# IPM_24V_24V.net
KiCad netlist of a schematic drawn in EasyEDA Pro
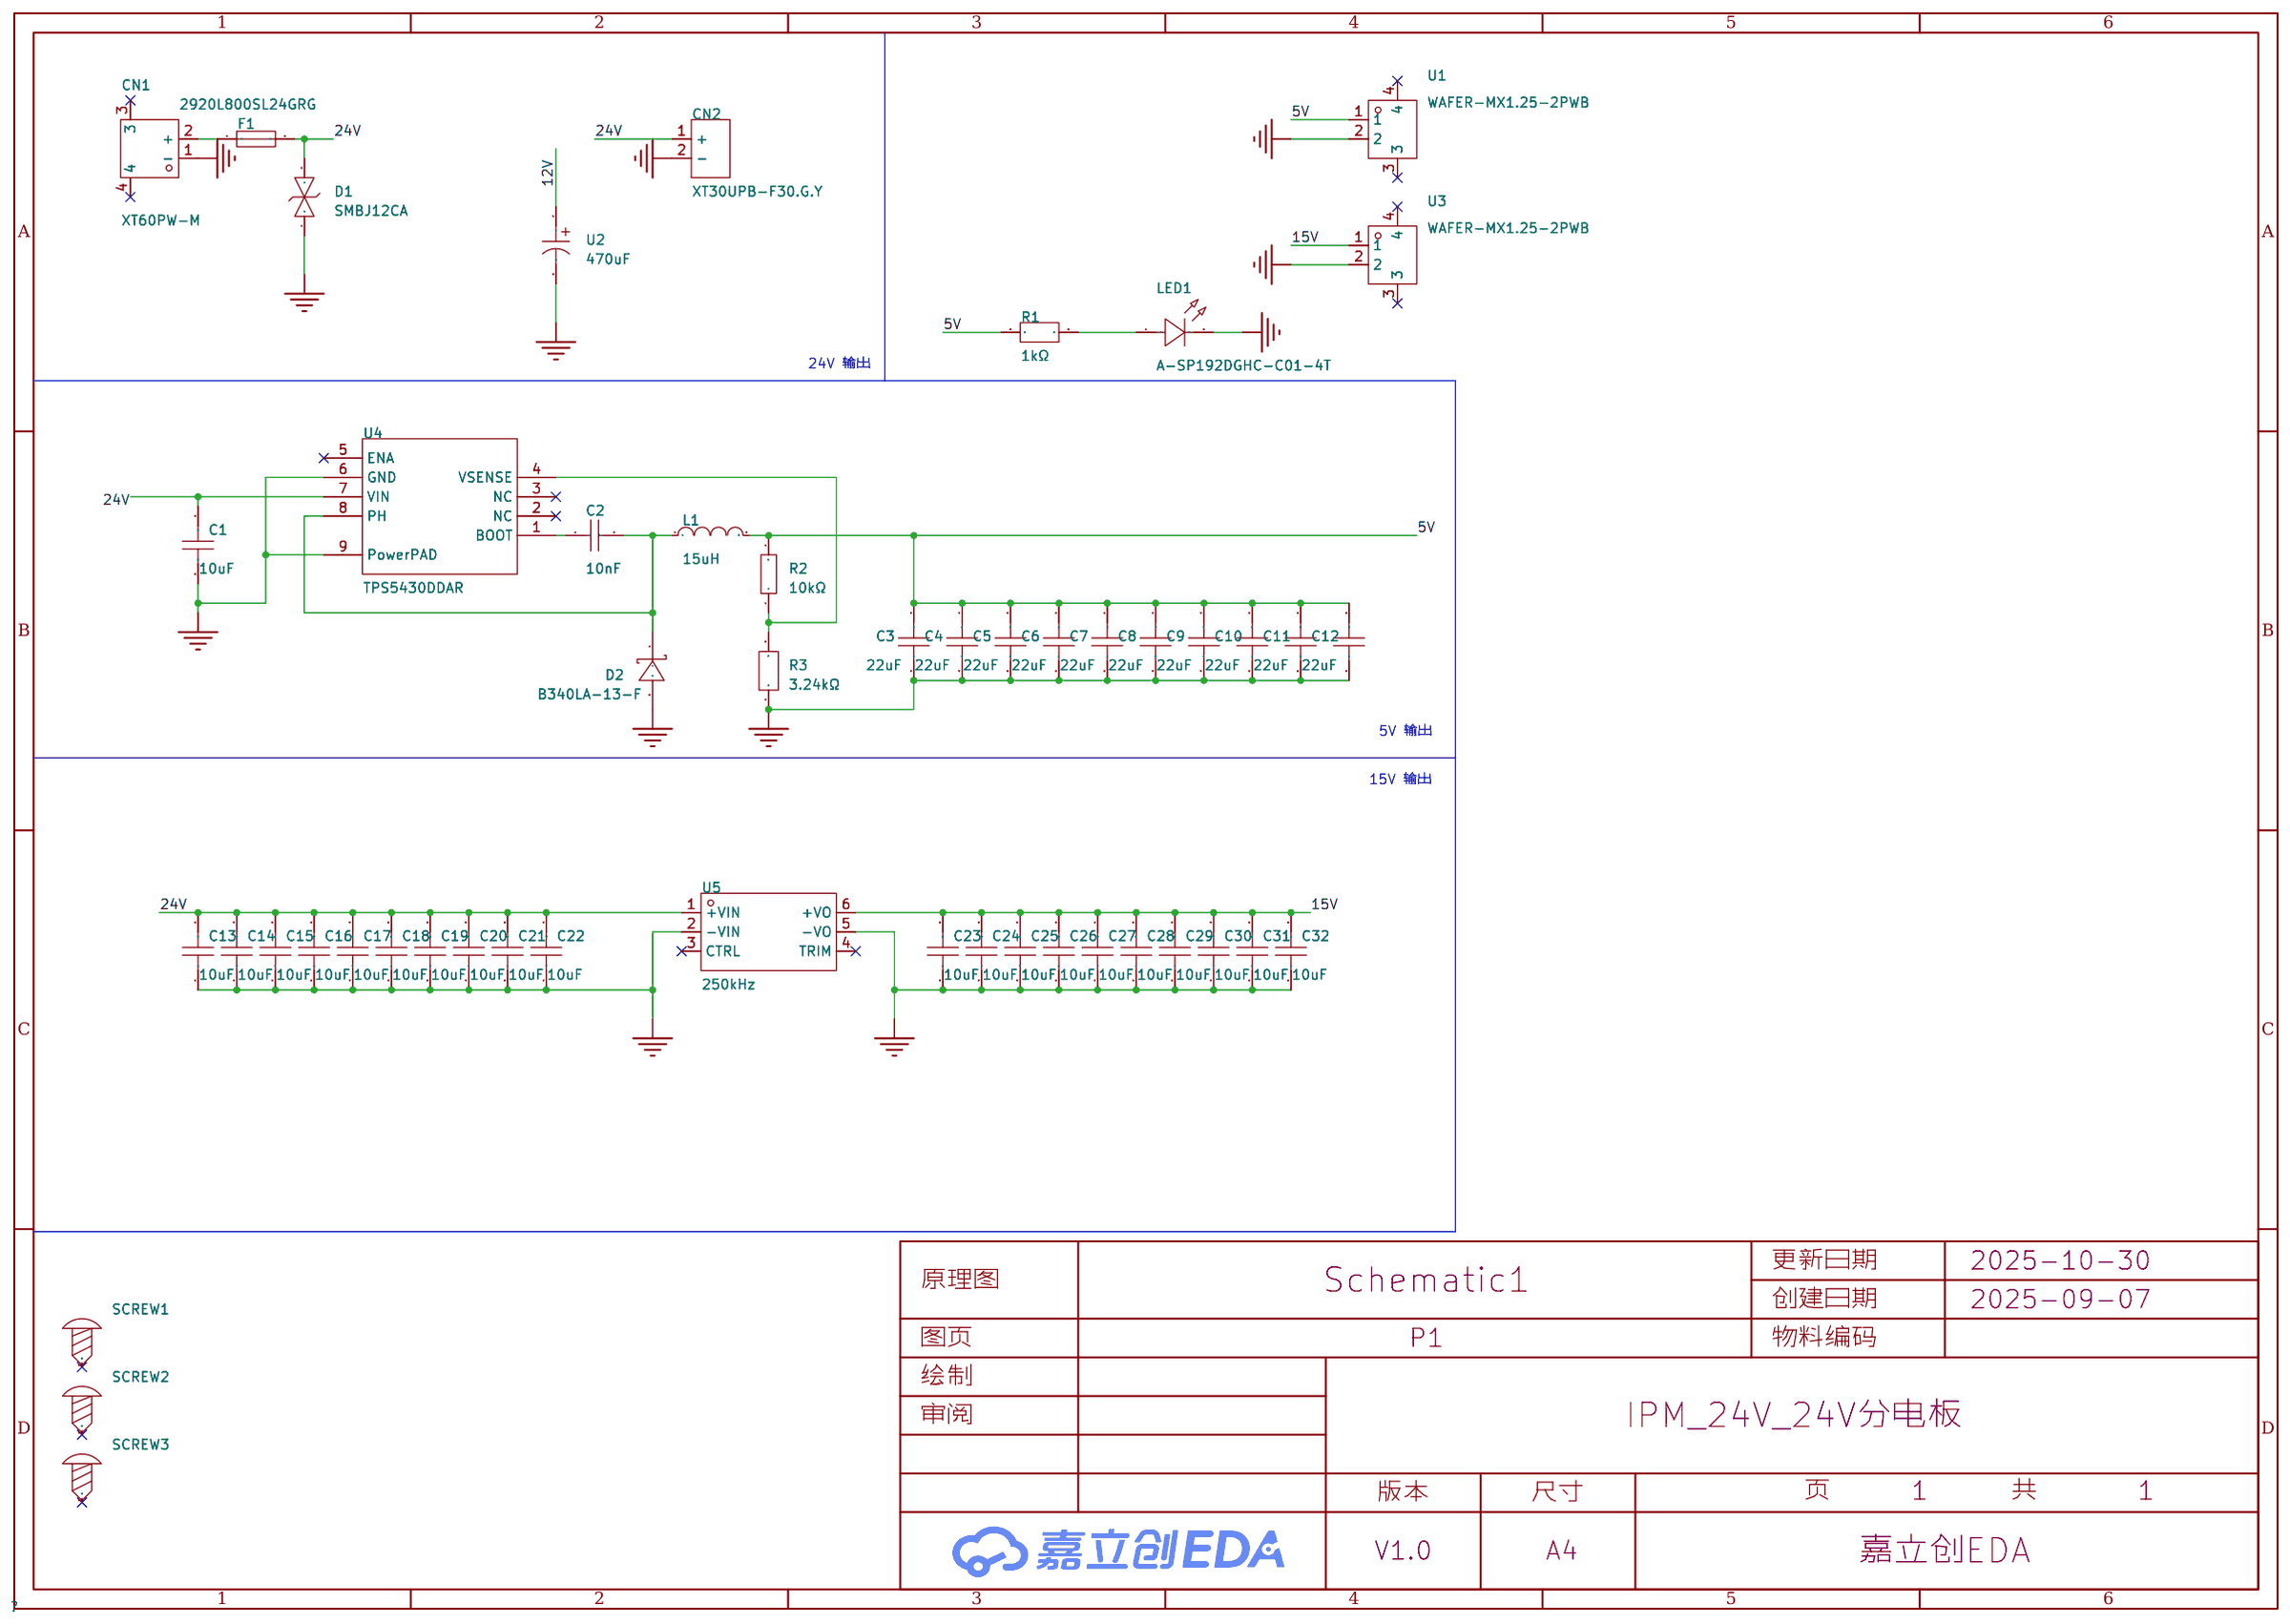
[diagram p0: schematic sheet]

(export (version "E")
  (design (tool "Eeschema 10.0.6"))
  (components
    (comp (ref "C1")
      (value "10uF")
      (footprint "easyedapro:C1206")
      (description "容值:10uF;精度:±10%;额定电压:50V;温度系数:X7R;")
      (fields
        (field (name "Manufacturer Part") "CL31B106KBHNNNE")
        (field (name "Manufacturer") "SAMSUNG(三星)")
      )
      (libsource (lib "easyedapro") (part "CL31B106KBHNNNE"))
    )
    (comp (ref "C2")
      (value "10nF")
      (footprint "easyedapro:C0603")
      (description "容值:10nF;精度:±10%;额定电压:50V;温度系数:X7R;")
      (fields
        (field (name "Manufacturer Part") "CL10B103KB8NNNC")
        (field (name "Manufacturer") "SAMSUNG(三星)")
      )
      (libsource (lib "easyedapro") (part "CL10B103KB8NNNC"))
    )
    (comp (ref "C3")
      (value "22uF")
      (footprint "easyedapro:C0603")
      (description "容值:22uF;精度:±20%;额定电压:16V;温度系数:X5R;")
      (fields
        (field (name "Manufacturer Part") "CL10A226MO7JZNC")
        (field (name "Manufacturer") "SAMSUNG(三星)")
      )
      (libsource (lib "easyedapro") (part "CL10A226MO7JZNC"))
    )
    (comp (ref "C4")
      (value "22uF")
      (footprint "easyedapro:C0603")
      (description "容值:22uF;精度:±20%;额定电压:16V;温度系数:X5R;")
      (fields
        (field (name "Manufacturer Part") "CL10A226MO7JZNC")
        (field (name "Manufacturer") "SAMSUNG(三星)")
      )
      (libsource (lib "easyedapro") (part "CL10A226MO7JZNC"))
    )
    (comp (ref "C5")
      (value "22uF")
      (footprint "easyedapro:C0603")
      (description "容值:22uF;精度:±20%;额定电压:16V;温度系数:X5R;")
      (fields
        (field (name "Manufacturer Part") "CL10A226MO7JZNC")
        (field (name "Manufacturer") "SAMSUNG(三星)")
      )
      (libsource (lib "easyedapro") (part "CL10A226MO7JZNC"))
    )
    (comp (ref "C6")
      (value "22uF")
      (footprint "easyedapro:C0603")
      (description "容值:22uF;精度:±20%;额定电压:16V;温度系数:X5R;")
      (fields
        (field (name "Manufacturer Part") "CL10A226MO7JZNC")
        (field (name "Manufacturer") "SAMSUNG(三星)")
      )
      (libsource (lib "easyedapro") (part "CL10A226MO7JZNC"))
    )
    (comp (ref "C7")
      (value "22uF")
      (footprint "easyedapro:C0603")
      (description "容值:22uF;精度:±20%;额定电压:16V;温度系数:X5R;")
      (fields
        (field (name "Manufacturer Part") "CL10A226MO7JZNC")
        (field (name "Manufacturer") "SAMSUNG(三星)")
      )
      (libsource (lib "easyedapro") (part "CL10A226MO7JZNC"))
    )
    (comp (ref "C8")
      (value "22uF")
      (footprint "easyedapro:C0603")
      (description "容值:22uF;精度:±20%;额定电压:16V;温度系数:X5R;")
      (fields
        (field (name "Manufacturer Part") "CL10A226MO7JZNC")
        (field (name "Manufacturer") "SAMSUNG(三星)")
      )
      (libsource (lib "easyedapro") (part "CL10A226MO7JZNC"))
    )
    (comp (ref "C9")
      (value "22uF")
      (footprint "easyedapro:C0603")
      (description "容值:22uF;精度:±20%;额定电压:16V;温度系数:X5R;")
      (fields
        (field (name "Manufacturer Part") "CL10A226MO7JZNC")
        (field (name "Manufacturer") "SAMSUNG(三星)")
      )
      (libsource (lib "easyedapro") (part "CL10A226MO7JZNC"))
    )
    (comp (ref "C10")
      (value "22uF")
      (footprint "easyedapro:C0603")
      (description "容值:22uF;精度:±20%;额定电压:16V;温度系数:X5R;")
      (fields
        (field (name "Manufacturer Part") "CL10A226MO7JZNC")
        (field (name "Manufacturer") "SAMSUNG(三星)")
      )
      (libsource (lib "easyedapro") (part "CL10A226MO7JZNC"))
    )
    (comp (ref "C11")
      (value "22uF")
      (footprint "easyedapro:C0603")
      (description "容值:22uF;精度:±20%;额定电压:16V;温度系数:X5R;")
      (fields
        (field (name "Manufacturer Part") "CL10A226MO7JZNC")
        (field (name "Manufacturer") "SAMSUNG(三星)")
      )
      (libsource (lib "easyedapro") (part "CL10A226MO7JZNC"))
    )
    (comp (ref "C12")
      (value "22uF")
      (footprint "easyedapro:C0603")
      (description "容值:22uF;精度:±20%;额定电压:16V;温度系数:X5R;")
      (fields
        (field (name "Manufacturer Part") "CL10A226MO7JZNC")
        (field (name "Manufacturer") "SAMSUNG(三星)")
      )
      (libsource (lib "easyedapro") (part "CL10A226MO7JZNC"))
    )
    (comp (ref "C13")
      (value "10uF")
      (footprint "easyedapro:C1206")
      (description "容值:10uF;精度:±10%;额定电压:50V;温度系数:X7R;")
      (fields
        (field (name "Manufacturer Part") "CL31B106KBHNNNE")
        (field (name "Manufacturer") "SAMSUNG(三星)")
      )
      (libsource (lib "easyedapro") (part "CL31B106KBHNNNE"))
    )
    (comp (ref "C14")
      (value "10uF")
      (footprint "easyedapro:C1206")
      (description "容值:10uF;精度:±10%;额定电压:50V;温度系数:X7R;")
      (fields
        (field (name "Manufacturer Part") "CL31B106KBHNNNE")
        (field (name "Manufacturer") "SAMSUNG(三星)")
      )
      (libsource (lib "easyedapro") (part "CL31B106KBHNNNE"))
    )
    (comp (ref "C15")
      (value "10uF")
      (footprint "easyedapro:C1206")
      (description "容值:10uF;精度:±10%;额定电压:50V;温度系数:X7R;")
      (fields
        (field (name "Manufacturer Part") "CL31B106KBHNNNE")
        (field (name "Manufacturer") "SAMSUNG(三星)")
      )
      (libsource (lib "easyedapro") (part "CL31B106KBHNNNE"))
    )
    (comp (ref "C16")
      (value "10uF")
      (footprint "easyedapro:C1206")
      (description "容值:10uF;精度:±10%;额定电压:50V;温度系数:X7R;")
      (fields
        (field (name "Manufacturer Part") "CL31B106KBHNNNE")
        (field (name "Manufacturer") "SAMSUNG(三星)")
      )
      (libsource (lib "easyedapro") (part "CL31B106KBHNNNE"))
    )
    (comp (ref "C17")
      (value "10uF")
      (footprint "easyedapro:C1206")
      (description "容值:10uF;精度:±10%;额定电压:50V;温度系数:X7R;")
      (fields
        (field (name "Manufacturer Part") "CL31B106KBHNNNE")
        (field (name "Manufacturer") "SAMSUNG(三星)")
      )
      (libsource (lib "easyedapro") (part "CL31B106KBHNNNE"))
    )
    (comp (ref "C18")
      (value "10uF")
      (footprint "easyedapro:C1206")
      (description "容值:10uF;精度:±10%;额定电压:50V;温度系数:X7R;")
      (fields
        (field (name "Manufacturer Part") "CL31B106KBHNNNE")
        (field (name "Manufacturer") "SAMSUNG(三星)")
      )
      (libsource (lib "easyedapro") (part "CL31B106KBHNNNE"))
    )
    (comp (ref "C19")
      (value "10uF")
      (footprint "easyedapro:C1206")
      (description "容值:10uF;精度:±10%;额定电压:50V;温度系数:X7R;")
      (fields
        (field (name "Manufacturer Part") "CL31B106KBHNNNE")
        (field (name "Manufacturer") "SAMSUNG(三星)")
      )
      (libsource (lib "easyedapro") (part "CL31B106KBHNNNE"))
    )
    (comp (ref "C20")
      (value "10uF")
      (footprint "easyedapro:C1206")
      (description "容值:10uF;精度:±10%;额定电压:50V;温度系数:X7R;")
      (fields
        (field (name "Manufacturer Part") "CL31B106KBHNNNE")
        (field (name "Manufacturer") "SAMSUNG(三星)")
      )
      (libsource (lib "easyedapro") (part "CL31B106KBHNNNE"))
    )
    (comp (ref "C21")
      (value "10uF")
      (footprint "easyedapro:C1206")
      (description "容值:10uF;精度:±10%;额定电压:50V;温度系数:X7R;")
      (fields
        (field (name "Manufacturer Part") "CL31B106KBHNNNE")
        (field (name "Manufacturer") "SAMSUNG(三星)")
      )
      (libsource (lib "easyedapro") (part "CL31B106KBHNNNE"))
    )
    (comp (ref "C22")
      (value "10uF")
      (footprint "easyedapro:C1206")
      (description "容值:10uF;精度:±10%;额定电压:50V;温度系数:X7R;")
      (fields
        (field (name "Manufacturer Part") "CL31B106KBHNNNE")
        (field (name "Manufacturer") "SAMSUNG(三星)")
      )
      (libsource (lib "easyedapro") (part "CL31B106KBHNNNE"))
    )
    (comp (ref "C23")
      (value "10uF")
      (footprint "easyedapro:C1206")
      (description "容值:10uF;精度:±10%;额定电压:50V;温度系数:X7R;")
      (fields
        (field (name "Manufacturer Part") "CL31B106KBHNNNE")
        (field (name "Manufacturer") "SAMSUNG(三星)")
      )
      (libsource (lib "easyedapro") (part "CL31B106KBHNNNE"))
    )
    (comp (ref "C24")
      (value "10uF")
      (footprint "easyedapro:C1206")
      (description "容值:10uF;精度:±10%;额定电压:50V;温度系数:X7R;")
      (fields
        (field (name "Manufacturer Part") "CL31B106KBHNNNE")
        (field (name "Manufacturer") "SAMSUNG(三星)")
      )
      (libsource (lib "easyedapro") (part "CL31B106KBHNNNE"))
    )
    (comp (ref "C25")
      (value "10uF")
      (footprint "easyedapro:C1206")
      (description "容值:10uF;精度:±10%;额定电压:50V;温度系数:X7R;")
      (fields
        (field (name "Manufacturer Part") "CL31B106KBHNNNE")
        (field (name "Manufacturer") "SAMSUNG(三星)")
      )
      (libsource (lib "easyedapro") (part "CL31B106KBHNNNE"))
    )
    (comp (ref "C26")
      (value "10uF")
      (footprint "easyedapro:C1206")
      (description "容值:10uF;精度:±10%;额定电压:50V;温度系数:X7R;")
      (fields
        (field (name "Manufacturer Part") "CL31B106KBHNNNE")
        (field (name "Manufacturer") "SAMSUNG(三星)")
      )
      (libsource (lib "easyedapro") (part "CL31B106KBHNNNE"))
    )
    (comp (ref "C27")
      (value "10uF")
      (footprint "easyedapro:C1206")
      (description "容值:10uF;精度:±10%;额定电压:50V;温度系数:X7R;")
      (fields
        (field (name "Manufacturer Part") "CL31B106KBHNNNE")
        (field (name "Manufacturer") "SAMSUNG(三星)")
      )
      (libsource (lib "easyedapro") (part "CL31B106KBHNNNE"))
    )
    (comp (ref "C28")
      (value "10uF")
      (footprint "easyedapro:C1206")
      (description "容值:10uF;精度:±10%;额定电压:50V;温度系数:X7R;")
      (fields
        (field (name "Manufacturer Part") "CL31B106KBHNNNE")
        (field (name "Manufacturer") "SAMSUNG(三星)")
      )
      (libsource (lib "easyedapro") (part "CL31B106KBHNNNE"))
    )
    (comp (ref "C29")
      (value "10uF")
      (footprint "easyedapro:C1206")
      (description "容值:10uF;精度:±10%;额定电压:50V;温度系数:X7R;")
      (fields
        (field (name "Manufacturer Part") "CL31B106KBHNNNE")
        (field (name "Manufacturer") "SAMSUNG(三星)")
      )
      (libsource (lib "easyedapro") (part "CL31B106KBHNNNE"))
    )
    (comp (ref "C30")
      (value "10uF")
      (footprint "easyedapro:C1206")
      (description "容值:10uF;精度:±10%;额定电压:50V;温度系数:X7R;")
      (fields
        (field (name "Manufacturer Part") "CL31B106KBHNNNE")
        (field (name "Manufacturer") "SAMSUNG(三星)")
      )
      (libsource (lib "easyedapro") (part "CL31B106KBHNNNE"))
    )
    (comp (ref "C31")
      (value "10uF")
      (footprint "easyedapro:C1206")
      (description "容值:10uF;精度:±10%;额定电压:50V;温度系数:X7R;")
      (fields
        (field (name "Manufacturer Part") "CL31B106KBHNNNE")
        (field (name "Manufacturer") "SAMSUNG(三星)")
      )
      (libsource (lib "easyedapro") (part "CL31B106KBHNNNE"))
    )
    (comp (ref "C32")
      (value "10uF")
      (footprint "easyedapro:C1206")
      (description "容值:10uF;精度:±10%;额定电压:50V;温度系数:X7R;")
      (fields
        (field (name "Manufacturer Part") "CL31B106KBHNNNE")
        (field (name "Manufacturer") "SAMSUNG(三星)")
      )
      (libsource (lib "easyedapro") (part "CL31B106KBHNNNE"))
    )
    (comp (ref "CN1")
      (value "XT60PW-M")
      (footprint "easyedapro:CONN-TH_XT60PW-M")
      (description "类别:-;类型1:-;")
      (fields (field (name "Manufacturer") "AMASS(艾迈斯)"))
      (libsource (lib "easyedapro") (part "XT60PW-M"))
    )
    (comp (ref "CN2")
      (value "XT30UPB-F30.G.Y")
      (footprint "easyedapro:CONN-TH_XT30UPB-F")
      (description "类别:-;类型1:-;")
      (fields (field (name "Manufacturer") "AMASS(艾迈斯)"))
      (libsource (lib "easyedapro") (part "XT30UPB-F"))
    )
    (comp (ref "D1")
      (value "SMBJ12CA")
      (footprint "easyedapro:SMB_L4.6-W3.6-LS5.4-BI")
      (fields (field (name "Manufacturer") "R+O(宏嘉诚)"))
      (libsource (lib "easyedapro") (part "SMBJ12CA_C19077566"))
    )
    (comp (ref "D2")
      (value "B340LA-13-F")
      (footprint "easyedapro:SMA_L4.3-W2.6-LS5.2-RD")
      (description "正向压降(Vf):450mV@3A;直流反向耐压(Vr):40V;平均整流电流(Io):3A;")
      (fields (field (name "Manufacturer") "DIODES(美台)"))
      (libsource (lib "easyedapro") (part "B340LA-13-F"))
    )
    (comp (ref "F1")
      (value "2920L800SL24GRG")
      (footprint "easyedapro:F2920")
      (description "耐压(Vmax):24V;最大电流(Imax):50A;保持电流(Ihold):8A;跳闸电流(Itrip):16A;")
      (fields (field (name "Manufacturer") "LUTE(陆特)"))
      (libsource (lib "easyedapro") (part "2920L800SL24GRG"))
    )
    (comp (ref "L1")
      (value "15uH")
      (footprint "easyedapro:IND-SMD_L7.0-W6.6_FXL0630")
      (description "电感值:15uH;精度:±20%;额定电流:3A;饱和电流(Isat):4A;类型:一体成型电感;")
      (fields (field (name "Manufacturer Part") "FXL0630-150-M") (field (name "Manufacturer") "cjiang(长江微电)"))
      (libsource (lib "easyedapro") (part "FXL0630-150-M"))
    )
    (comp (ref "LED1")
      (value "A-SP192DGHC-C01-4T")
      (footprint "easyedapro:LED0603-FD")
      (fields (field (name "Manufacturer") "Amicc(欧密格光电)"))
      (libsource (lib "easyedapro") (part "A-SP192DGHC-C01-4T"))
    )
    (comp (ref "R1")
      (value "1kΩ")
      (footprint "easyedapro:R0603")
      (description "电阻类型:厚膜电阻;阻值:1kΩ;精度:±1%;功率:100mW;工作电压:75V;温度系数:±100ppm/°C;")
      (fields (field (name "Manufacturer Part") "FRC0603F1001TS") (field (name "Manufacturer") "FOJAN(富捷)"))
      (libsource (lib "easyedapro") (part "FRC0603F1001TS"))
    )
    (comp (ref "R2")
      (value "10kΩ")
      (footprint "easyedapro:R0603")
      (description "电阻类型:厚膜电阻;阻值:10kΩ;精度:±1%;功率:100mW;工作电压:75V;温度系数:±100ppm/°C;")
      (fields
        (field (name "Manufacturer Part") "0603WAF1002T5E")
        (field (name "Manufacturer") "UNI-ROYAL(厚声)")
      )
      (libsource (lib "easyedapro") (part "0603WAF1002T5E"))
    )
    (comp (ref "R3")
      (value "3.24kΩ")
      (footprint "easyedapro:R0603")
      (description "电阻类型:厚膜电阻;阻值:3.24kΩ;精度:±1%;功率:100mW;工作电压:75V;温度系数:±100ppm/°C;")
      (fields (field (name "Manufacturer Part") "FRC0603F3241TS") (field (name "Manufacturer") "FOJAN(富捷)"))
      (libsource (lib "easyedapro") (part "FRC0603F3241TS"))
    )
    (comp (ref "SCREW1")
      (value "~")
      (footprint "easyedapro:M2螺丝")
      (libsource (lib "easyedapro") (part "螺丝孔"))
    )
    (comp (ref "SCREW2")
      (value "~")
      (footprint "easyedapro:M2螺丝")
      (libsource (lib "easyedapro") (part "螺丝孔"))
    )
    (comp (ref "SCREW3")
      (value "~")
      (footprint "easyedapro:M2螺丝")
      (libsource (lib "easyedapro") (part "螺丝孔"))
    )
    (comp (ref "U1")
      (value "WAFER-MX1.25-2PWB")
      (footprint "easyedapro:CONN-SMD_2P-P1.25_XUNPU_WAFER-MX1.25-2PWB")
      (fields (field (name "Manufacturer") "XUNPU(讯普)"))
      (libsource (lib "easyedapro") (part "WAFER-MX1.25-2PWB"))
    )
    (comp (ref "U2")
      (value "470uF")
      (footprint "easyedapro:CAP-TH_BD10.0-P5.00-D1.0-FD")
      (description "容值:470uF;精度:±20%;额定电压:50V;纹波电流:-;等效串联电阻(ESR):-;")
      (fields
        (field (name "Manufacturer Part") "ERJ1HM471G16C36T")
        (field (name "Manufacturer") "AISHI(艾华集团)")
      )
      (libsource (lib "easyedapro") (part "ERJ1HM471G16C36T"))
    )
    (comp (ref "U3")
      (value "WAFER-MX1.25-2PWB")
      (footprint "easyedapro:CONN-SMD_2P-P1.25_XUNPU_WAFER-MX1.25-2PWB")
      (fields (field (name "Manufacturer") "XUNPU(讯普)"))
      (libsource (lib "easyedapro") (part "WAFER-MX1.25-2PWB"))
    )
    (comp (ref "U4")
      (value "TPS5430DDAR")
      (footprint "easyedapro:ESOP-8_L4.9-W3.9-P1.27-LS6.0-TL-EP")
      (description "功能类型:降压型;输出类型:可调;工作电压:5.5V~36V;输出电压:1.221V~32.04V;输出电流:3A;")
      (fields (field (name "Manufacturer") "TI(德州仪器)"))
      (libsource (lib "easyedapro") (part "TPS5430DDAR"))
    )
    (comp (ref "U5")
      (value "250kHz")
      (footprint "easyedapro:PWRM-TH_URB2415LD-30WR3")
      (fields (field (name "Manufacturer Part") "URB2415LD-30WR3") (field (name "Manufacturer") "YLPTEC(易川)"))
      (libsource (lib "easyedapro") (part "URB2415LD-30WR3_C5369835"))
    )
  )
  (nets
    (net (code "1") (name "/5V") (class "Default")
      (node (ref "C10") (pin "1") (pinfunction "1_1") (pintype "unspecified"))
      (node (ref "C11") (pin "1") (pinfunction "1_1") (pintype "unspecified"))
      (node (ref "C12") (pin "1") (pinfunction "1_1") (pintype "unspecified"))
      (node (ref "C3") (pin "1") (pinfunction "1_1") (pintype "unspecified"))
      (node (ref "C4") (pin "1") (pinfunction "1_1") (pintype "unspecified"))
      (node (ref "C5") (pin "1") (pinfunction "1_1") (pintype "unspecified"))
      (node (ref "C6") (pin "1") (pinfunction "1_1") (pintype "unspecified"))
      (node (ref "C7") (pin "1") (pinfunction "1_1") (pintype "unspecified"))
      (node (ref "C8") (pin "1") (pinfunction "1_1") (pintype "unspecified"))
      (node (ref "C9") (pin "1") (pinfunction "1_1") (pintype "unspecified"))
      (node (ref "L1") (pin "2") (pinfunction "2_2") (pintype "unspecified"))
      (node (ref "R1") (pin "1") (pinfunction "1_1") (pintype "unspecified"))
      (node (ref "R2") (pin "2") (pinfunction "2_2") (pintype "input"))
      (node (ref "U1") (pin "1") (pinfunction "1_1") (pintype "unspecified"))
    )
    (net (code "2") (name "/12V") (class "Default")
      (node (ref "U2") (pin "1") (pinfunction "1_1") (pintype "input"))
    )
    (net (code "3") (name "/15V") (class "Default")
      (node (ref "C23") (pin "2") (pinfunction "2_2") (pintype "unspecified"))
      (node (ref "C24") (pin "2") (pinfunction "2_2") (pintype "unspecified"))
      (node (ref "C25") (pin "2") (pinfunction "2_2") (pintype "unspecified"))
      (node (ref "C26") (pin "2") (pinfunction "2_2") (pintype "unspecified"))
      (node (ref "C27") (pin "2") (pinfunction "2_2") (pintype "unspecified"))
      (node (ref "C28") (pin "2") (pinfunction "2_2") (pintype "unspecified"))
      (node (ref "C29") (pin "2") (pinfunction "2_2") (pintype "unspecified"))
      (node (ref "C30") (pin "2") (pinfunction "2_2") (pintype "unspecified"))
      (node (ref "C31") (pin "2") (pinfunction "2_2") (pintype "unspecified"))
      (node (ref "C32") (pin "2") (pinfunction "2_2") (pintype "unspecified"))
      (node (ref "U3") (pin "1") (pinfunction "1_1") (pintype "unspecified"))
      (node (ref "U5") (pin "6") (pinfunction "+VO_6") (pintype "unspecified"))
    )
    (net (code "4") (name "/24V") (class "Default")
      (node (ref "C1") (pin "2") (pinfunction "2_2") (pintype "unspecified"))
      (node (ref "C13") (pin "2") (pinfunction "2_2") (pintype "unspecified"))
      (node (ref "C14") (pin "2") (pinfunction "2_2") (pintype "unspecified"))
      (node (ref "C15") (pin "2") (pinfunction "2_2") (pintype "unspecified"))
      (node (ref "C16") (pin "2") (pinfunction "2_2") (pintype "unspecified"))
      (node (ref "C17") (pin "2") (pinfunction "2_2") (pintype "unspecified"))
      (node (ref "C18") (pin "2") (pinfunction "2_2") (pintype "unspecified"))
      (node (ref "C19") (pin "2") (pinfunction "2_2") (pintype "unspecified"))
      (node (ref "C20") (pin "2") (pinfunction "2_2") (pintype "unspecified"))
      (node (ref "C21") (pin "2") (pinfunction "2_2") (pintype "unspecified"))
      (node (ref "C22") (pin "2") (pinfunction "2_2") (pintype "unspecified"))
      (node (ref "CN2") (pin "1") (pinfunction "+_1") (pintype "unspecified"))
      (node (ref "D1") (pin "2") (pinfunction "2_2") (pintype "unspecified"))
      (node (ref "F1") (pin "2") (pinfunction "2_2") (pintype "unspecified"))
      (node (ref "U4") (pin "7") (pinfunction "VIN_7") (pintype "unspecified"))
      (node (ref "U5") (pin "1") (pinfunction "+VIN_1") (pintype "unspecified"))
    )
    (net (code "5") (name "GND") (class "Default")
      (node (ref "C1") (pin "1") (pinfunction "1_1") (pintype "unspecified"))
      (node (ref "C10") (pin "2") (pinfunction "2_2") (pintype "unspecified"))
      (node (ref "C11") (pin "2") (pinfunction "2_2") (pintype "unspecified"))
      (node (ref "C12") (pin "2") (pinfunction "2_2") (pintype "unspecified"))
      (node (ref "C13") (pin "1") (pinfunction "1_1") (pintype "unspecified"))
      (node (ref "C14") (pin "1") (pinfunction "1_1") (pintype "unspecified"))
      (node (ref "C15") (pin "1") (pinfunction "1_1") (pintype "unspecified"))
      (node (ref "C16") (pin "1") (pinfunction "1_1") (pintype "unspecified"))
      (node (ref "C17") (pin "1") (pinfunction "1_1") (pintype "unspecified"))
      (node (ref "C18") (pin "1") (pinfunction "1_1") (pintype "unspecified"))
      (node (ref "C19") (pin "1") (pinfunction "1_1") (pintype "unspecified"))
      (node (ref "C20") (pin "1") (pinfunction "1_1") (pintype "unspecified"))
      (node (ref "C21") (pin "1") (pinfunction "1_1") (pintype "unspecified"))
      (node (ref "C22") (pin "1") (pinfunction "1_1") (pintype "unspecified"))
      (node (ref "C23") (pin "1") (pinfunction "1_1") (pintype "unspecified"))
      (node (ref "C24") (pin "1") (pinfunction "1_1") (pintype "unspecified"))
      (node (ref "C25") (pin "1") (pinfunction "1_1") (pintype "unspecified"))
      (node (ref "C26") (pin "1") (pinfunction "1_1") (pintype "unspecified"))
      (node (ref "C27") (pin "1") (pinfunction "1_1") (pintype "unspecified"))
      (node (ref "C28") (pin "1") (pinfunction "1_1") (pintype "unspecified"))
      (node (ref "C29") (pin "1") (pinfunction "1_1") (pintype "unspecified"))
      (node (ref "C3") (pin "2") (pinfunction "2_2") (pintype "unspecified"))
      (node (ref "C30") (pin "1") (pinfunction "1_1") (pintype "unspecified"))
      (node (ref "C31") (pin "1") (pinfunction "1_1") (pintype "unspecified"))
      (node (ref "C32") (pin "1") (pinfunction "1_1") (pintype "unspecified"))
      (node (ref "C4") (pin "2") (pinfunction "2_2") (pintype "unspecified"))
      (node (ref "C5") (pin "2") (pinfunction "2_2") (pintype "unspecified"))
      (node (ref "C6") (pin "2") (pinfunction "2_2") (pintype "unspecified"))
      (node (ref "C7") (pin "2") (pinfunction "2_2") (pintype "unspecified"))
      (node (ref "C8") (pin "2") (pinfunction "2_2") (pintype "unspecified"))
      (node (ref "C9") (pin "2") (pinfunction "2_2") (pintype "unspecified"))
      (node (ref "CN1") (pin "1") (pinfunction "-_1") (pintype "unspecified"))
      (node (ref "CN2") (pin "2") (pinfunction "-_2") (pintype "unspecified"))
      (node (ref "D1") (pin "1") (pinfunction "1_1") (pintype "unspecified"))
      (node (ref "D2") (pin "2") (pinfunction "A_2") (pintype "unspecified"))
      (node (ref "LED1") (pin "2") (pinfunction "K_2") (pintype "unspecified"))
      (node (ref "R3") (pin "1") (pinfunction "1_1") (pintype "unspecified"))
      (node (ref "U1") (pin "2") (pinfunction "2_2") (pintype "unspecified"))
      (node (ref "U2") (pin "2") (pinfunction "2_2") (pintype "input"))
      (node (ref "U3") (pin "2") (pinfunction "2_2") (pintype "unspecified"))
      (node (ref "U4") (pin "6") (pinfunction "GND_6") (pintype "unspecified"))
      (node (ref "U4") (pin "9") (pinfunction "PowerPAD_9") (pintype "unspecified"))
      (node (ref "U5") (pin "2") (pinfunction "-VIN_2") (pintype "unspecified"))
      (node (ref "U5") (pin "5") (pinfunction "-VO_5") (pintype "unspecified"))
    )
    (net (code "6") (name "Net-(CN1-+)") (class "Default")
      (node (ref "CN1") (pin "2") (pinfunction "+_2") (pintype "unspecified"))
      (node (ref "F1") (pin "1") (pinfunction "1_1") (pintype "unspecified"))
    )
    (net (code "7") (name "Net-(D2-K)") (class "Default")
      (node (ref "C2") (pin "2") (pinfunction "2_2") (pintype "input"))
      (node (ref "D2") (pin "1") (pinfunction "K_1") (pintype "unspecified"))
      (node (ref "L1") (pin "1") (pinfunction "1_1") (pintype "unspecified"))
      (node (ref "U4") (pin "8") (pinfunction "PH_8") (pintype "unspecified"))
    )
    (net (code "8") (name "Net-(LED1-A)") (class "Default")
      (node (ref "LED1") (pin "1") (pinfunction "A_1") (pintype "unspecified"))
      (node (ref "R1") (pin "2") (pinfunction "2_2") (pintype "unspecified"))
    )
    (net (code "9") (name "Net-(U4-BOOT)") (class "Default")
      (node (ref "C2") (pin "1") (pinfunction "1_1") (pintype "input"))
      (node (ref "U4") (pin "1") (pinfunction "BOOT_1") (pintype "unspecified"))
    )
    (net (code "10") (name "Net-(U4-VSENSE)") (class "Default")
      (node (ref "R2") (pin "1") (pinfunction "1_1") (pintype "input"))
      (node (ref "R3") (pin "2") (pinfunction "2_2") (pintype "unspecified"))
      (node (ref "U4") (pin "4") (pinfunction "VSENSE_4") (pintype "unspecified"))
    )
    (net (code "11") (name "unconnected-(CN1-Pad3)") (class "Default")
      (node (ref "CN1") (pin "3") (pinfunction "3_3") (pintype "unspecified+no_connect"))
    )
    (net (code "12") (name "unconnected-(CN1-Pad4)") (class "Default")
      (node (ref "CN1") (pin "4") (pinfunction "4_4") (pintype "unspecified+no_connect"))
    )
    (net (code "13") (name "unconnected-(SCREW1-Pad1)") (class "Default")
      (node (ref "SCREW1") (pin "1") (pinfunction "1_1") (pintype "input+no_connect"))
    )
    (net (code "14") (name "unconnected-(SCREW2-Pad1)") (class "Default")
      (node (ref "SCREW2") (pin "1") (pinfunction "1_1") (pintype "input+no_connect"))
    )
    (net (code "15") (name "unconnected-(SCREW3-Pad1)") (class "Default")
      (node (ref "SCREW3") (pin "1") (pinfunction "1_1") (pintype "input+no_connect"))
    )
    (net (code "16") (name "unconnected-(U1-Pad3)") (class "Default")
      (node (ref "U1") (pin "3") (pinfunction "3_3") (pintype "unspecified+no_connect"))
    )
    (net (code "17") (name "unconnected-(U1-Pad4)") (class "Default")
      (node (ref "U1") (pin "4") (pinfunction "4_4") (pintype "unspecified+no_connect"))
    )
    (net (code "18") (name "unconnected-(U3-Pad3)") (class "Default")
      (node (ref "U3") (pin "3") (pinfunction "3_3") (pintype "unspecified+no_connect"))
    )
    (net (code "19") (name "unconnected-(U3-Pad4)") (class "Default")
      (node (ref "U3") (pin "4") (pinfunction "4_4") (pintype "unspecified+no_connect"))
    )
    (net (code "20") (name "unconnected-(U4-ENA-Pad5)") (class "Default")
      (node (ref "U4") (pin "5") (pinfunction "ENA_5") (pintype "unspecified+no_connect"))
    )
    (net (code "21") (name "unconnected-(U4-NC-Pad2)") (class "Default")
      (node (ref "U4") (pin "2") (pinfunction "NC_2") (pintype "unspecified+no_connect"))
    )
    (net (code "22") (name "unconnected-(U4-NC-Pad3)") (class "Default")
      (node (ref "U4") (pin "3") (pinfunction "NC_3") (pintype "unspecified+no_connect"))
    )
    (net (code "23") (name "unconnected-(U5-CTRL-Pad3)") (class "Default")
      (node (ref "U5") (pin "3") (pinfunction "CTRL_3") (pintype "unspecified+no_connect"))
    )
    (net (code "24") (name "unconnected-(U5-TRIM-Pad4)") (class "Default")
      (node (ref "U5") (pin "4") (pinfunction "TRIM_4") (pintype "unspecified+no_connect"))
    )
  )
)
